# esphome-schalter-4x4.net
KiCad netlist of a schematic drawn in EAGLE
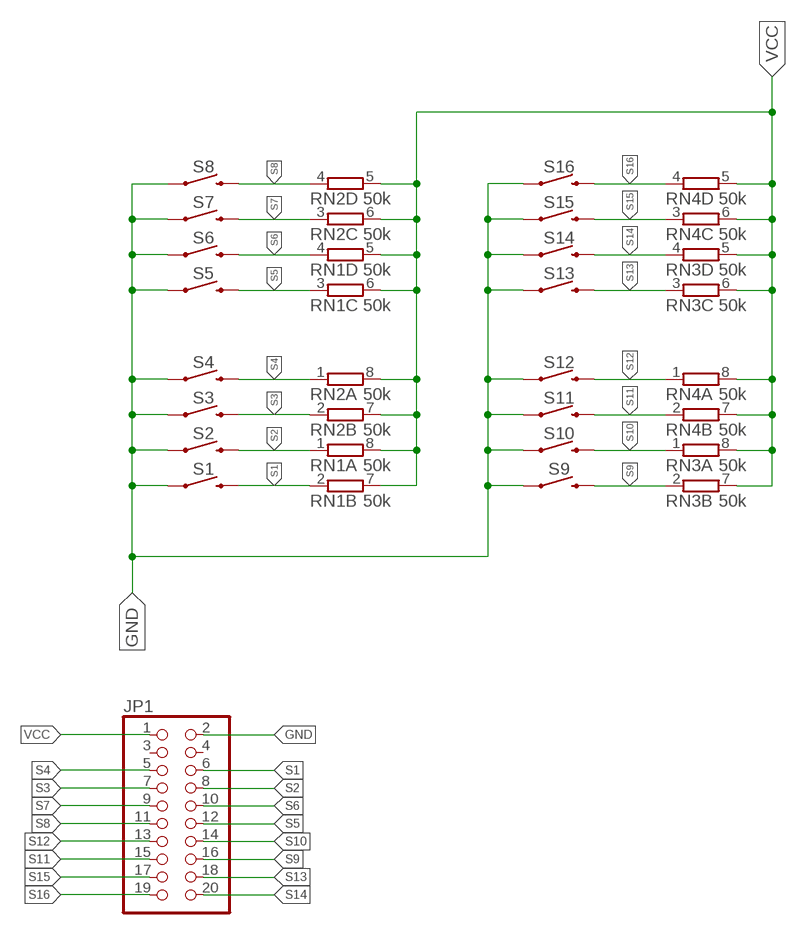
[diagram p0: schematic, sheet 1]

(export (version "E")
  (design (tool "Eeschema 10.0.6"))
  (components
    (comp (ref "JP1")
      (value "PINHD-2X10")
      (footprint "eagle-import:2X10")
      (libsource (lib "eagle-import") (part "PINHD-2X10"))
    )
    (comp (ref "RN1")
      (value "50k")
      (footprint "eagle-import:EXBS8V")
      (libsource (lib "eagle-import") (part "4R-NEXBS8V"))
    )
    (comp (ref "RN2")
      (value "50k")
      (footprint "eagle-import:EXBS8V")
      (libsource (lib "eagle-import") (part "4R-NEXBS8V"))
    )
    (comp (ref "RN3")
      (value "50k")
      (footprint "eagle-import:EXBS8V")
      (libsource (lib "eagle-import") (part "4R-NEXBS8V"))
    )
    (comp (ref "RN4")
      (value "50k")
      (footprint "eagle-import:EXBS8V")
      (libsource (lib "eagle-import") (part "4R-NEXBS8V"))
    )
    (comp (ref "S1")
      (value "MOMENTARY-SWITCH-SPST-PTH-6.0MM")
      (footprint "eagle-import:TACTILE_SWITCH_PTH_6.0MM")
      (libsource (lib "eagle-import") (part "MOMENTARY-SWITCH-SPST-PTH-6.0MM"))
    )
    (comp (ref "S2")
      (value "MOMENTARY-SWITCH-SPST-PTH-6.0MM")
      (footprint "eagle-import:TACTILE_SWITCH_PTH_6.0MM")
      (libsource (lib "eagle-import") (part "MOMENTARY-SWITCH-SPST-PTH-6.0MM"))
    )
    (comp (ref "S3")
      (value "MOMENTARY-SWITCH-SPST-PTH-6.0MM")
      (footprint "eagle-import:TACTILE_SWITCH_PTH_6.0MM")
      (libsource (lib "eagle-import") (part "MOMENTARY-SWITCH-SPST-PTH-6.0MM"))
    )
    (comp (ref "S4")
      (value "MOMENTARY-SWITCH-SPST-PTH-6.0MM")
      (footprint "eagle-import:TACTILE_SWITCH_PTH_6.0MM")
      (libsource (lib "eagle-import") (part "MOMENTARY-SWITCH-SPST-PTH-6.0MM"))
    )
    (comp (ref "S5")
      (value "MOMENTARY-SWITCH-SPST-PTH-6.0MM")
      (footprint "eagle-import:TACTILE_SWITCH_PTH_6.0MM")
      (libsource (lib "eagle-import") (part "MOMENTARY-SWITCH-SPST-PTH-6.0MM"))
    )
    (comp (ref "S6")
      (value "MOMENTARY-SWITCH-SPST-PTH-6.0MM")
      (footprint "eagle-import:TACTILE_SWITCH_PTH_6.0MM")
      (libsource (lib "eagle-import") (part "MOMENTARY-SWITCH-SPST-PTH-6.0MM"))
    )
    (comp (ref "S7")
      (value "MOMENTARY-SWITCH-SPST-PTH-6.0MM")
      (footprint "eagle-import:TACTILE_SWITCH_PTH_6.0MM")
      (libsource (lib "eagle-import") (part "MOMENTARY-SWITCH-SPST-PTH-6.0MM"))
    )
    (comp (ref "S8")
      (value "MOMENTARY-SWITCH-SPST-PTH-6.0MM")
      (footprint "eagle-import:TACTILE_SWITCH_PTH_6.0MM")
      (libsource (lib "eagle-import") (part "MOMENTARY-SWITCH-SPST-PTH-6.0MM"))
    )
    (comp (ref "S9")
      (value "MOMENTARY-SWITCH-SPST-PTH-6.0MM")
      (footprint "eagle-import:TACTILE_SWITCH_PTH_6.0MM")
      (libsource (lib "eagle-import") (part "MOMENTARY-SWITCH-SPST-PTH-6.0MM"))
    )
    (comp (ref "S10")
      (value "MOMENTARY-SWITCH-SPST-PTH-6.0MM")
      (footprint "eagle-import:TACTILE_SWITCH_PTH_6.0MM")
      (libsource (lib "eagle-import") (part "MOMENTARY-SWITCH-SPST-PTH-6.0MM"))
    )
    (comp (ref "S11")
      (value "MOMENTARY-SWITCH-SPST-PTH-6.0MM")
      (footprint "eagle-import:TACTILE_SWITCH_PTH_6.0MM")
      (libsource (lib "eagle-import") (part "MOMENTARY-SWITCH-SPST-PTH-6.0MM"))
    )
    (comp (ref "S12")
      (value "MOMENTARY-SWITCH-SPST-PTH-6.0MM")
      (footprint "eagle-import:TACTILE_SWITCH_PTH_6.0MM")
      (libsource (lib "eagle-import") (part "MOMENTARY-SWITCH-SPST-PTH-6.0MM"))
    )
    (comp (ref "S13")
      (value "MOMENTARY-SWITCH-SPST-PTH-6.0MM")
      (footprint "eagle-import:TACTILE_SWITCH_PTH_6.0MM")
      (libsource (lib "eagle-import") (part "MOMENTARY-SWITCH-SPST-PTH-6.0MM"))
    )
    (comp (ref "S14")
      (value "MOMENTARY-SWITCH-SPST-PTH-6.0MM")
      (footprint "eagle-import:TACTILE_SWITCH_PTH_6.0MM")
      (libsource (lib "eagle-import") (part "MOMENTARY-SWITCH-SPST-PTH-6.0MM"))
    )
    (comp (ref "S15")
      (value "MOMENTARY-SWITCH-SPST-PTH-6.0MM")
      (footprint "eagle-import:TACTILE_SWITCH_PTH_6.0MM")
      (libsource (lib "eagle-import") (part "MOMENTARY-SWITCH-SPST-PTH-6.0MM"))
    )
    (comp (ref "S16")
      (value "MOMENTARY-SWITCH-SPST-PTH-6.0MM")
      (footprint "eagle-import:TACTILE_SWITCH_PTH_6.0MM")
      (libsource (lib "eagle-import") (part "MOMENTARY-SWITCH-SPST-PTH-6.0MM"))
    )
  )
  (nets
    (net (code "1") (name "GND") (class "Default")
      (node (ref "JP1") (pin "2") (pinfunction "2_2") (pintype "passive"))
      (node (ref "S1") (pin "1") (pinfunction "1_1") (pintype "passive"))
      (node (ref "S10") (pin "1") (pinfunction "1_1") (pintype "passive"))
      (node (ref "S11") (pin "1") (pinfunction "1_1") (pintype "passive"))
      (node (ref "S12") (pin "1") (pinfunction "1_1") (pintype "passive"))
      (node (ref "S13") (pin "1") (pinfunction "1_1") (pintype "passive"))
      (node (ref "S14") (pin "1") (pinfunction "1_1") (pintype "passive"))
      (node (ref "S15") (pin "1") (pinfunction "1_1") (pintype "passive"))
      (node (ref "S16") (pin "1") (pinfunction "1_1") (pintype "passive"))
      (node (ref "S2") (pin "1") (pinfunction "1_1") (pintype "passive"))
      (node (ref "S3") (pin "1") (pinfunction "1_1") (pintype "passive"))
      (node (ref "S4") (pin "1") (pinfunction "1_1") (pintype "passive"))
      (node (ref "S5") (pin "1") (pinfunction "1_1") (pintype "passive"))
      (node (ref "S6") (pin "1") (pinfunction "1_1") (pintype "passive"))
      (node (ref "S7") (pin "1") (pinfunction "1_1") (pintype "passive"))
      (node (ref "S8") (pin "1") (pinfunction "1_1") (pintype "passive"))
      (node (ref "S9") (pin "1") (pinfunction "1_1") (pintype "passive"))
    )
    (net (code "2") (name "S1") (class "Default")
      (node (ref "JP1") (pin "6") (pinfunction "6_6") (pintype "passive"))
      (node (ref "RN1") (pin "2") (pinfunction "1_2") (pintype "passive"))
      (node (ref "S1") (pin "3") (pinfunction "2_3") (pintype "passive"))
    )
    (net (code "3") (name "S2") (class "Default")
      (node (ref "JP1") (pin "8") (pinfunction "8_8") (pintype "passive"))
      (node (ref "RN1") (pin "1") (pinfunction "1_1") (pintype "passive"))
      (node (ref "S2") (pin "3") (pinfunction "2_3") (pintype "passive"))
    )
    (net (code "4") (name "S3") (class "Default")
      (node (ref "JP1") (pin "7") (pinfunction "7_7") (pintype "passive"))
      (node (ref "RN2") (pin "2") (pinfunction "1_2") (pintype "passive"))
      (node (ref "S3") (pin "3") (pinfunction "2_3") (pintype "passive"))
    )
    (net (code "5") (name "S4") (class "Default")
      (node (ref "JP1") (pin "5") (pinfunction "5_5") (pintype "passive"))
      (node (ref "RN2") (pin "1") (pinfunction "1_1") (pintype "passive"))
      (node (ref "S4") (pin "3") (pinfunction "2_3") (pintype "passive"))
    )
    (net (code "6") (name "S5") (class "Default")
      (node (ref "JP1") (pin "12") (pinfunction "12_12") (pintype "passive"))
      (node (ref "RN1") (pin "3") (pinfunction "1_3") (pintype "passive"))
      (node (ref "S5") (pin "3") (pinfunction "2_3") (pintype "passive"))
    )
    (net (code "7") (name "S6") (class "Default")
      (node (ref "JP1") (pin "10") (pinfunction "10_10") (pintype "passive"))
      (node (ref "RN1") (pin "4") (pinfunction "1_4") (pintype "passive"))
      (node (ref "S6") (pin "3") (pinfunction "2_3") (pintype "passive"))
    )
    (net (code "8") (name "S7") (class "Default")
      (node (ref "JP1") (pin "9") (pinfunction "9_9") (pintype "passive"))
      (node (ref "RN2") (pin "3") (pinfunction "1_3") (pintype "passive"))
      (node (ref "S7") (pin "3") (pinfunction "2_3") (pintype "passive"))
    )
    (net (code "9") (name "S8") (class "Default")
      (node (ref "JP1") (pin "11") (pinfunction "11_11") (pintype "passive"))
      (node (ref "RN2") (pin "4") (pinfunction "1_4") (pintype "passive"))
      (node (ref "S8") (pin "3") (pinfunction "2_3") (pintype "passive"))
    )
    (net (code "10") (name "S9") (class "Default")
      (node (ref "JP1") (pin "16") (pinfunction "16_16") (pintype "passive"))
      (node (ref "RN3") (pin "2") (pinfunction "1_2") (pintype "passive"))
      (node (ref "S9") (pin "3") (pinfunction "2_3") (pintype "passive"))
    )
    (net (code "11") (name "S10") (class "Default")
      (node (ref "JP1") (pin "14") (pinfunction "14_14") (pintype "passive"))
      (node (ref "RN3") (pin "1") (pinfunction "1_1") (pintype "passive"))
      (node (ref "S10") (pin "3") (pinfunction "2_3") (pintype "passive"))
    )
    (net (code "12") (name "S11") (class "Default")
      (node (ref "JP1") (pin "15") (pinfunction "15_15") (pintype "passive"))
      (node (ref "RN4") (pin "2") (pinfunction "1_2") (pintype "passive"))
      (node (ref "S11") (pin "3") (pinfunction "2_3") (pintype "passive"))
    )
    (net (code "13") (name "S12") (class "Default")
      (node (ref "JP1") (pin "13") (pinfunction "13_13") (pintype "passive"))
      (node (ref "RN4") (pin "1") (pinfunction "1_1") (pintype "passive"))
      (node (ref "S12") (pin "3") (pinfunction "2_3") (pintype "passive"))
    )
    (net (code "14") (name "S13") (class "Default")
      (node (ref "JP1") (pin "18") (pinfunction "18_18") (pintype "passive"))
      (node (ref "RN3") (pin "3") (pinfunction "1_3") (pintype "passive"))
      (node (ref "S13") (pin "3") (pinfunction "2_3") (pintype "passive"))
    )
    (net (code "15") (name "S14") (class "Default")
      (node (ref "JP1") (pin "20") (pinfunction "20_20") (pintype "passive"))
      (node (ref "RN3") (pin "4") (pinfunction "1_4") (pintype "passive"))
      (node (ref "S14") (pin "3") (pinfunction "2_3") (pintype "passive"))
    )
    (net (code "16") (name "S15") (class "Default")
      (node (ref "JP1") (pin "17") (pinfunction "17_17") (pintype "passive"))
      (node (ref "RN4") (pin "3") (pinfunction "1_3") (pintype "passive"))
      (node (ref "S15") (pin "3") (pinfunction "2_3") (pintype "passive"))
    )
    (net (code "17") (name "S16") (class "Default")
      (node (ref "JP1") (pin "19") (pinfunction "19_19") (pintype "passive"))
      (node (ref "RN4") (pin "4") (pinfunction "1_4") (pintype "passive"))
      (node (ref "S16") (pin "3") (pinfunction "2_3") (pintype "passive"))
    )
    (net (code "18") (name "VCC") (class "Default")
      (node (ref "JP1") (pin "1") (pinfunction "1_1") (pintype "passive"))
      (node (ref "RN1") (pin "5") (pinfunction "2_5") (pintype "passive"))
      (node (ref "RN1") (pin "6") (pinfunction "2_6") (pintype "passive"))
      (node (ref "RN1") (pin "7") (pinfunction "2_7") (pintype "passive"))
      (node (ref "RN1") (pin "8") (pinfunction "2_8") (pintype "passive"))
      (node (ref "RN2") (pin "5") (pinfunction "2_5") (pintype "passive"))
      (node (ref "RN2") (pin "6") (pinfunction "2_6") (pintype "passive"))
      (node (ref "RN2") (pin "7") (pinfunction "2_7") (pintype "passive"))
      (node (ref "RN2") (pin "8") (pinfunction "2_8") (pintype "passive"))
      (node (ref "RN3") (pin "5") (pinfunction "2_5") (pintype "passive"))
      (node (ref "RN3") (pin "6") (pinfunction "2_6") (pintype "passive"))
      (node (ref "RN3") (pin "7") (pinfunction "2_7") (pintype "passive"))
      (node (ref "RN3") (pin "8") (pinfunction "2_8") (pintype "passive"))
      (node (ref "RN4") (pin "5") (pinfunction "2_5") (pintype "passive"))
      (node (ref "RN4") (pin "6") (pinfunction "2_6") (pintype "passive"))
      (node (ref "RN4") (pin "7") (pinfunction "2_7") (pintype "passive"))
      (node (ref "RN4") (pin "8") (pinfunction "2_8") (pintype "passive"))
    )
    (net (code "19") (name "unconnected-(JP1-Pad3)") (class "Default")
      (node (ref "JP1") (pin "3") (pinfunction "3_3") (pintype "passive"))
    )
    (net (code "20") (name "unconnected-(JP1-Pad4)") (class "Default")
      (node (ref "JP1") (pin "4") (pinfunction "4_4") (pintype "passive"))
    )
  )
)
